# drumuino.net
KiCad netlist of a schematic drawn in EAGLE
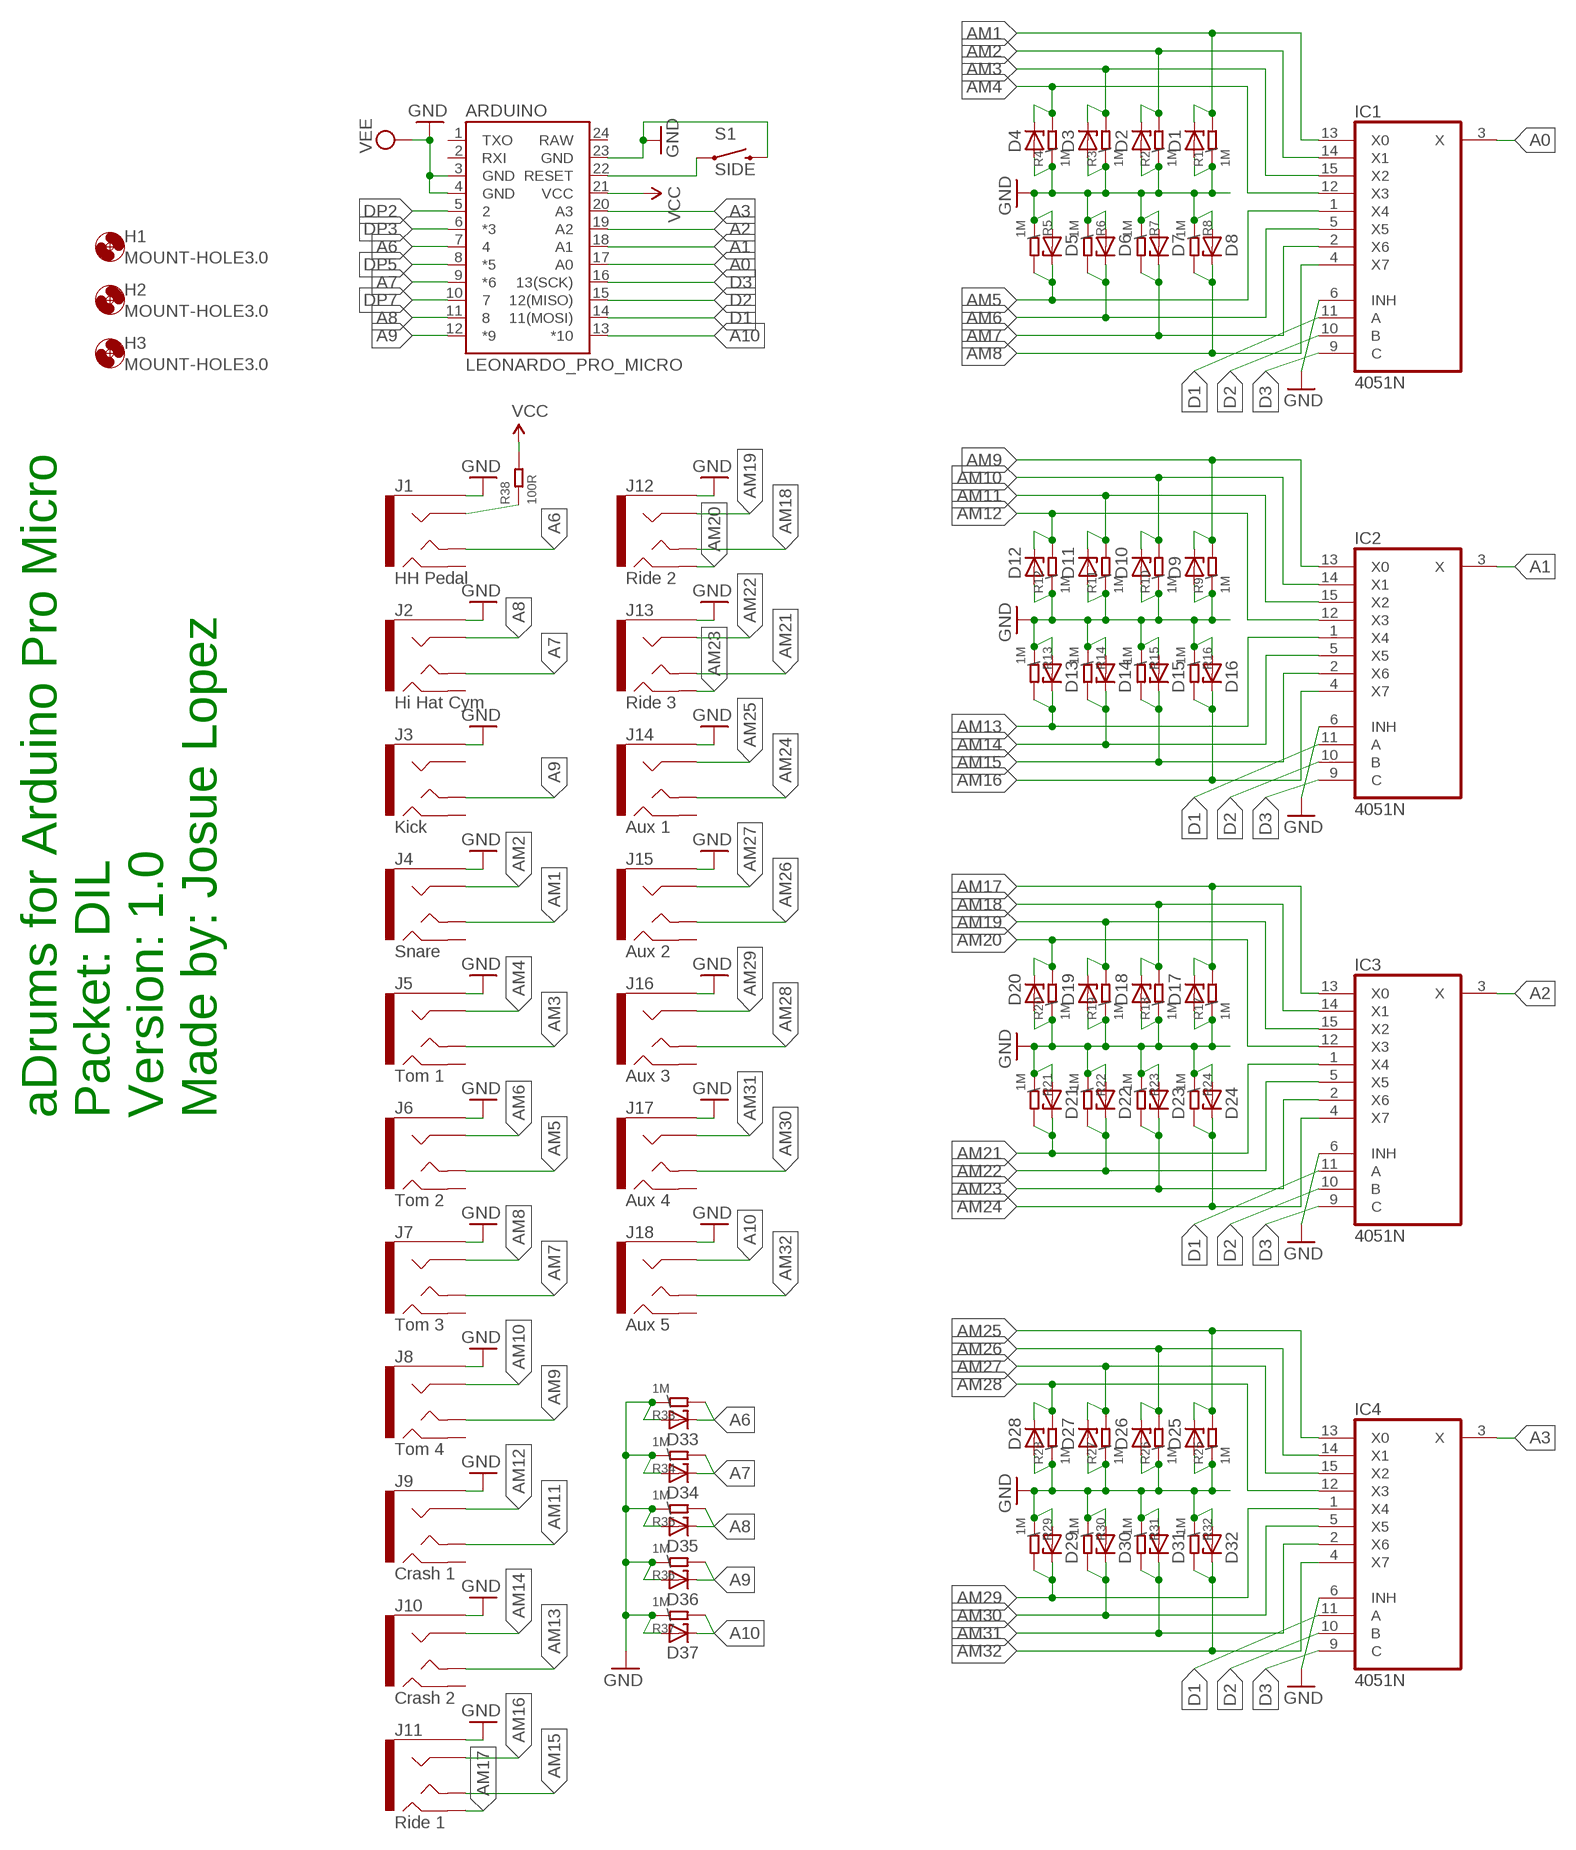
[diagram p0: schematic, sheet 1]

(export (version "E")
  (design (tool "Eeschema 10.0.6"))
  (components
    (comp (ref "ARDUINO")
      (value "LEONARDO_PRO_MICRO")
      (footprint "eagle-import:ARDUINO_PRO_MICRO")
      (libsource (lib "eagle-import") (part "ARDUINO_PRO_MICRO"))
    )
    (comp (ref "D1")
      (value "\\")
      (footprint "eagle-import:DO41-7.6")
      (libsource (lib "eagle-import") (part "ZENER-DIODEDO41-7.6"))
    )
    (comp (ref "D2")
      (value "\\")
      (footprint "eagle-import:DO41-7.6")
      (libsource (lib "eagle-import") (part "ZENER-DIODEDO41-7.6"))
    )
    (comp (ref "D3")
      (value "\\")
      (footprint "eagle-import:DO41-7.6")
      (libsource (lib "eagle-import") (part "ZENER-DIODEDO41-7.6"))
    )
    (comp (ref "D4")
      (value "\\")
      (footprint "eagle-import:DO41-7.6")
      (libsource (lib "eagle-import") (part "ZENER-DIODEDO41-7.6"))
    )
    (comp (ref "D5")
      (value "\\")
      (footprint "eagle-import:DO41-7.6")
      (libsource (lib "eagle-import") (part "ZENER-DIODEDO41-7.6"))
    )
    (comp (ref "D6")
      (value "\\")
      (footprint "eagle-import:DO41-7.6")
      (libsource (lib "eagle-import") (part "ZENER-DIODEDO41-7.6"))
    )
    (comp (ref "D7")
      (value "\\")
      (footprint "eagle-import:DO41-7.6")
      (libsource (lib "eagle-import") (part "ZENER-DIODEDO41-7.6"))
    )
    (comp (ref "D8")
      (value "\\")
      (footprint "eagle-import:DO41-7.6")
      (libsource (lib "eagle-import") (part "ZENER-DIODEDO41-7.6"))
    )
    (comp (ref "D9")
      (value "\\")
      (footprint "eagle-import:DO41-7.6")
      (libsource (lib "eagle-import") (part "ZENER-DIODEDO41-7.6"))
    )
    (comp (ref "D10")
      (value "\\")
      (footprint "eagle-import:DO41-7.6")
      (libsource (lib "eagle-import") (part "ZENER-DIODEDO41-7.6"))
    )
    (comp (ref "D11")
      (value "\\")
      (footprint "eagle-import:DO41-7.6")
      (libsource (lib "eagle-import") (part "ZENER-DIODEDO41-7.6"))
    )
    (comp (ref "D12")
      (value "\\")
      (footprint "eagle-import:DO41-7.6")
      (libsource (lib "eagle-import") (part "ZENER-DIODEDO41-7.6"))
    )
    (comp (ref "D13")
      (value "\\")
      (footprint "eagle-import:DO41-7.6")
      (libsource (lib "eagle-import") (part "ZENER-DIODEDO41-7.6"))
    )
    (comp (ref "D14")
      (value "\\")
      (footprint "eagle-import:DO41-7.6")
      (libsource (lib "eagle-import") (part "ZENER-DIODEDO41-7.6"))
    )
    (comp (ref "D15")
      (value "\\")
      (footprint "eagle-import:DO41-7.6")
      (libsource (lib "eagle-import") (part "ZENER-DIODEDO41-7.6"))
    )
    (comp (ref "D16")
      (value "\\")
      (footprint "eagle-import:DO41-7.6")
      (libsource (lib "eagle-import") (part "ZENER-DIODEDO41-7.6"))
    )
    (comp (ref "D17")
      (value "\\")
      (footprint "eagle-import:DO41-7.6")
      (libsource (lib "eagle-import") (part "ZENER-DIODEDO41-7.6"))
    )
    (comp (ref "D18")
      (value "\\")
      (footprint "eagle-import:DO41-7.6")
      (libsource (lib "eagle-import") (part "ZENER-DIODEDO41-7.6"))
    )
    (comp (ref "D19")
      (value "\\")
      (footprint "eagle-import:DO41-7.6")
      (libsource (lib "eagle-import") (part "ZENER-DIODEDO41-7.6"))
    )
    (comp (ref "D20")
      (value "\\")
      (footprint "eagle-import:DO41-7.6")
      (libsource (lib "eagle-import") (part "ZENER-DIODEDO41-7.6"))
    )
    (comp (ref "D21")
      (value "\\")
      (footprint "eagle-import:DO41-7.6")
      (libsource (lib "eagle-import") (part "ZENER-DIODEDO41-7.6"))
    )
    (comp (ref "D22")
      (value "\\")
      (footprint "eagle-import:DO41-7.6")
      (libsource (lib "eagle-import") (part "ZENER-DIODEDO41-7.6"))
    )
    (comp (ref "D23")
      (value "\\")
      (footprint "eagle-import:DO41-7.6")
      (libsource (lib "eagle-import") (part "ZENER-DIODEDO41-7.6"))
    )
    (comp (ref "D24")
      (value "\\")
      (footprint "eagle-import:DO41-7.6")
      (libsource (lib "eagle-import") (part "ZENER-DIODEDO41-7.6"))
    )
    (comp (ref "D25")
      (value "\\")
      (footprint "eagle-import:DO41-7.6")
      (libsource (lib "eagle-import") (part "ZENER-DIODEDO41-7.6"))
    )
    (comp (ref "D26")
      (value "\\")
      (footprint "eagle-import:DO41-7.6")
      (libsource (lib "eagle-import") (part "ZENER-DIODEDO41-7.6"))
    )
    (comp (ref "D27")
      (value "\\")
      (footprint "eagle-import:DO41-7.6")
      (libsource (lib "eagle-import") (part "ZENER-DIODEDO41-7.6"))
    )
    (comp (ref "D28")
      (value "\\")
      (footprint "eagle-import:DO41-7.6")
      (libsource (lib "eagle-import") (part "ZENER-DIODEDO41-7.6"))
    )
    (comp (ref "D29")
      (value "\\")
      (footprint "eagle-import:DO41-7.6")
      (libsource (lib "eagle-import") (part "ZENER-DIODEDO41-7.6"))
    )
    (comp (ref "D30")
      (value "\\")
      (footprint "eagle-import:DO41-7.6")
      (libsource (lib "eagle-import") (part "ZENER-DIODEDO41-7.6"))
    )
    (comp (ref "D31")
      (value "\\")
      (footprint "eagle-import:DO41-7.6")
      (libsource (lib "eagle-import") (part "ZENER-DIODEDO41-7.6"))
    )
    (comp (ref "D32")
      (value "\\")
      (footprint "eagle-import:DO41-7.6")
      (libsource (lib "eagle-import") (part "ZENER-DIODEDO41-7.6"))
    )
    (comp (ref "D33")
      (value "\\")
      (footprint "eagle-import:DO41-7.6")
      (libsource (lib "eagle-import") (part "ZENER-DIODEDO41-7.6"))
    )
    (comp (ref "D34")
      (value "\\")
      (footprint "eagle-import:DO41-7.6")
      (libsource (lib "eagle-import") (part "ZENER-DIODEDO41-7.6"))
    )
    (comp (ref "D35")
      (value "\\")
      (footprint "eagle-import:DO41-7.6")
      (libsource (lib "eagle-import") (part "ZENER-DIODEDO41-7.6"))
    )
    (comp (ref "D36")
      (value "\\")
      (footprint "eagle-import:DO41-7.6")
      (libsource (lib "eagle-import") (part "ZENER-DIODEDO41-7.6"))
    )
    (comp (ref "D37")
      (value "\\")
      (footprint "eagle-import:DO41-7.6")
      (libsource (lib "eagle-import") (part "ZENER-DIODEDO41-7.6"))
    )
    (comp (ref "H1")
      (value "MOUNT-HOLE3.0")
      (footprint "eagle-import:3,0")
      (libsource (lib "eagle-import") (part "MOUNT-HOLE3.0"))
    )
    (comp (ref "H2")
      (value "MOUNT-HOLE3.0")
      (footprint "eagle-import:3,0")
      (libsource (lib "eagle-import") (part "MOUNT-HOLE3.0"))
    )
    (comp (ref "H3")
      (value "MOUNT-HOLE3.0")
      (footprint "eagle-import:3,0")
      (libsource (lib "eagle-import") (part "MOUNT-HOLE3.0"))
    )
    (comp (ref "IC1")
      (value "4051N")
      (footprint "eagle-import:DIL16")
      (libsource (lib "eagle-import") (part "4051N"))
    )
    (comp (ref "IC2")
      (value "4051N")
      (footprint "eagle-import:DIL16")
      (libsource (lib "eagle-import") (part "4051N"))
    )
    (comp (ref "IC3")
      (value "4051N")
      (footprint "eagle-import:DIL16")
      (libsource (lib "eagle-import") (part "4051N"))
    )
    (comp (ref "IC4")
      (value "4051N")
      (footprint "eagle-import:DIL16")
      (libsource (lib "eagle-import") (part "4051N"))
    )
    (comp (ref "J1")
      (value "HH Pedal")
      (footprint "eagle-import:AUDIO-JACK-TRRS-DIL")
      (libsource (lib "eagle-import") (part "AUDIO-JACK3'DIL'"))
    )
    (comp (ref "J2")
      (value "Hi Hat Cym")
      (footprint "eagle-import:AUDIO-JACK-TRRS-DIL")
      (libsource (lib "eagle-import") (part "AUDIO-JACK3'DIL'"))
    )
    (comp (ref "J3")
      (value "Kick")
      (footprint "eagle-import:AUDIO-JACK-TRRS-DIL")
      (libsource (lib "eagle-import") (part "AUDIO-JACK3'DIL'"))
    )
    (comp (ref "J4")
      (value "Snare")
      (footprint "eagle-import:AUDIO-JACK-TRRS-DIL")
      (libsource (lib "eagle-import") (part "AUDIO-JACK3'DIL'"))
    )
    (comp (ref "J5")
      (value "Tom 1")
      (footprint "eagle-import:AUDIO-JACK-TRRS-DIL")
      (libsource (lib "eagle-import") (part "AUDIO-JACK3'DIL'"))
    )
    (comp (ref "J6")
      (value "Tom 2")
      (footprint "eagle-import:AUDIO-JACK-TRRS-DIL")
      (libsource (lib "eagle-import") (part "AUDIO-JACK3'DIL'"))
    )
    (comp (ref "J7")
      (value "Tom 3")
      (footprint "eagle-import:AUDIO-JACK-TRRS-DIL")
      (libsource (lib "eagle-import") (part "AUDIO-JACK3'DIL'"))
    )
    (comp (ref "J8")
      (value "Tom 4")
      (footprint "eagle-import:AUDIO-JACK-TRRS-DIL")
      (libsource (lib "eagle-import") (part "AUDIO-JACK3'DIL'"))
    )
    (comp (ref "J9")
      (value "Crash 1")
      (footprint "eagle-import:AUDIO-JACK-TRRS-DIL")
      (libsource (lib "eagle-import") (part "AUDIO-JACK3'DIL'"))
    )
    (comp (ref "J10")
      (value "Crash 2")
      (footprint "eagle-import:AUDIO-JACK-TRRS-DIL")
      (libsource (lib "eagle-import") (part "AUDIO-JACK3'DIL'"))
    )
    (comp (ref "J11")
      (value "Ride 1")
      (footprint "eagle-import:AUDIO-JACK-TRRS-DIL")
      (libsource (lib "eagle-import") (part "AUDIO-JACK3'DIL'"))
    )
    (comp (ref "J12")
      (value "Ride 2")
      (footprint "eagle-import:AUDIO-JACK-TRRS-DIL")
      (libsource (lib "eagle-import") (part "AUDIO-JACK3'DIL'"))
    )
    (comp (ref "J13")
      (value "Ride 3")
      (footprint "eagle-import:AUDIO-JACK-TRRS-DIL")
      (libsource (lib "eagle-import") (part "AUDIO-JACK3'DIL'"))
    )
    (comp (ref "J14")
      (value "Aux 1")
      (footprint "eagle-import:AUDIO-JACK-TRRS-DIL")
      (libsource (lib "eagle-import") (part "AUDIO-JACK3'DIL'"))
    )
    (comp (ref "J15")
      (value "Aux 2")
      (footprint "eagle-import:AUDIO-JACK-TRRS-DIL")
      (libsource (lib "eagle-import") (part "AUDIO-JACK3'DIL'"))
    )
    (comp (ref "J16")
      (value "Aux 3")
      (footprint "eagle-import:AUDIO-JACK-TRRS-DIL")
      (libsource (lib "eagle-import") (part "AUDIO-JACK3'DIL'"))
    )
    (comp (ref "J17")
      (value "Aux 4")
      (footprint "eagle-import:AUDIO-JACK-TRRS-DIL")
      (libsource (lib "eagle-import") (part "AUDIO-JACK3'DIL'"))
    )
    (comp (ref "J18")
      (value "Aux 5")
      (footprint "eagle-import:AUDIO-JACK-TRRS-DIL")
      (libsource (lib "eagle-import") (part "AUDIO-JACK3'DIL'"))
    )
    (comp (ref "R1")
      (value "1M")
      (footprint "eagle-import:R0207_7")
      (libsource (lib "eagle-import") (part "RES-0207/7"))
    )
    (comp (ref "R2")
      (value "1M")
      (footprint "eagle-import:R0207_7")
      (libsource (lib "eagle-import") (part "RES-0207/7"))
    )
    (comp (ref "R3")
      (value "1M")
      (footprint "eagle-import:R0207_7")
      (libsource (lib "eagle-import") (part "RES-0207/7"))
    )
    (comp (ref "R4")
      (value "1M")
      (footprint "eagle-import:R0207_7")
      (libsource (lib "eagle-import") (part "RES-0207/7"))
    )
    (comp (ref "R5")
      (value "1M")
      (footprint "eagle-import:R0207_7")
      (libsource (lib "eagle-import") (part "RES-0207/7"))
    )
    (comp (ref "R6")
      (value "1M")
      (footprint "eagle-import:R0207_7")
      (libsource (lib "eagle-import") (part "RES-0207/7"))
    )
    (comp (ref "R7")
      (value "1M")
      (footprint "eagle-import:R0207_7")
      (libsource (lib "eagle-import") (part "RES-0207/7"))
    )
    (comp (ref "R8")
      (value "1M")
      (footprint "eagle-import:R0207_7")
      (libsource (lib "eagle-import") (part "RES-0207/7"))
    )
    (comp (ref "R9")
      (value "1M")
      (footprint "eagle-import:R0207_7")
      (libsource (lib "eagle-import") (part "RES-0207/7"))
    )
    (comp (ref "R10")
      (value "1M")
      (footprint "eagle-import:R0207_7")
      (libsource (lib "eagle-import") (part "RES-0207/7"))
    )
    (comp (ref "R11")
      (value "1M")
      (footprint "eagle-import:R0207_7")
      (libsource (lib "eagle-import") (part "RES-0207/7"))
    )
    (comp (ref "R12")
      (value "1M")
      (footprint "eagle-import:R0207_7")
      (libsource (lib "eagle-import") (part "RES-0207/7"))
    )
    (comp (ref "R13")
      (value "1M")
      (footprint "eagle-import:R0207_7")
      (libsource (lib "eagle-import") (part "RES-0207/7"))
    )
    (comp (ref "R14")
      (value "1M")
      (footprint "eagle-import:R0207_7")
      (libsource (lib "eagle-import") (part "RES-0207/7"))
    )
    (comp (ref "R15")
      (value "1M")
      (footprint "eagle-import:R0207_7")
      (libsource (lib "eagle-import") (part "RES-0207/7"))
    )
    (comp (ref "R16")
      (value "1M")
      (footprint "eagle-import:R0207_7")
      (libsource (lib "eagle-import") (part "RES-0207/7"))
    )
    (comp (ref "R17")
      (value "1M")
      (footprint "eagle-import:R0207_7")
      (libsource (lib "eagle-import") (part "RES-0207/7"))
    )
    (comp (ref "R18")
      (value "1M")
      (footprint "eagle-import:R0207_7")
      (libsource (lib "eagle-import") (part "RES-0207/7"))
    )
    (comp (ref "R19")
      (value "1M")
      (footprint "eagle-import:R0207_7")
      (libsource (lib "eagle-import") (part "RES-0207/7"))
    )
    (comp (ref "R20")
      (value "1M")
      (footprint "eagle-import:R0207_7")
      (libsource (lib "eagle-import") (part "RES-0207/7"))
    )
    (comp (ref "R21")
      (value "1M")
      (footprint "eagle-import:R0207_7")
      (libsource (lib "eagle-import") (part "RES-0207/7"))
    )
    (comp (ref "R22")
      (value "1M")
      (footprint "eagle-import:R0207_7")
      (libsource (lib "eagle-import") (part "RES-0207/7"))
    )
    (comp (ref "R23")
      (value "1M")
      (footprint "eagle-import:R0207_7")
      (libsource (lib "eagle-import") (part "RES-0207/7"))
    )
    (comp (ref "R24")
      (value "1M")
      (footprint "eagle-import:R0207_7")
      (libsource (lib "eagle-import") (part "RES-0207/7"))
    )
    (comp (ref "R25")
      (value "1M")
      (footprint "eagle-import:R0207_7")
      (libsource (lib "eagle-import") (part "RES-0207/7"))
    )
    (comp (ref "R26")
      (value "1M")
      (footprint "eagle-import:R0207_7")
      (libsource (lib "eagle-import") (part "RES-0207/7"))
    )
    (comp (ref "R27")
      (value "1M")
      (footprint "eagle-import:R0207_7")
      (libsource (lib "eagle-import") (part "RES-0207/7"))
    )
    (comp (ref "R28")
      (value "1M")
      (footprint "eagle-import:R0207_7")
      (libsource (lib "eagle-import") (part "RES-0207/7"))
    )
    (comp (ref "R29")
      (value "1M")
      (footprint "eagle-import:R0207_7")
      (libsource (lib "eagle-import") (part "RES-0207/7"))
    )
    (comp (ref "R30")
      (value "1M")
      (footprint "eagle-import:R0207_7")
      (libsource (lib "eagle-import") (part "RES-0207/7"))
    )
    (comp (ref "R31")
      (value "1M")
      (footprint "eagle-import:R0207_7")
      (libsource (lib "eagle-import") (part "RES-0207/7"))
    )
    (comp (ref "R32")
      (value "1M")
      (footprint "eagle-import:R0207_7")
      (libsource (lib "eagle-import") (part "RES-0207/7"))
    )
    (comp (ref "R33")
      (value "1M")
      (footprint "eagle-import:R0207_7")
      (libsource (lib "eagle-import") (part "RES-0207/7"))
    )
    (comp (ref "R34")
      (value "1M")
      (footprint "eagle-import:R0207_7")
      (libsource (lib "eagle-import") (part "RES-0207/7"))
    )
    (comp (ref "R35")
      (value "1M")
      (footprint "eagle-import:R0207_7")
      (libsource (lib "eagle-import") (part "RES-0207/7"))
    )
    (comp (ref "R36")
      (value "1M")
      (footprint "eagle-import:R0207_7")
      (libsource (lib "eagle-import") (part "RES-0207/7"))
    )
    (comp (ref "R37")
      (value "1M")
      (footprint "eagle-import:R0207_7")
      (libsource (lib "eagle-import") (part "RES-0207/7"))
    )
    (comp (ref "R38")
      (value "100R")
      (footprint "eagle-import:R0207_7")
      (libsource (lib "eagle-import") (part "RES-0207/7"))
    )
    (comp (ref "S1")
      (value "SIDE")
      (footprint "eagle-import:TACTILE-PTH-SIDEEZ")
      (libsource (lib "eagle-import") (part "SWITCH-MOMENTARY-2SIDE_EZ"))
    )
  )
  (nets
    (net (code "1") (name "A0") (class "Default")
      (node (ref "ARDUINO") (pin "17") (pinfunction "A0_17") (pintype "bidirectional"))
      (node (ref "IC1") (pin "3") (pinfunction "X_3") (pintype "bidirectional"))
    )
    (net (code "2") (name "A1") (class "Default")
      (node (ref "ARDUINO") (pin "18") (pinfunction "A1_18") (pintype "bidirectional"))
      (node (ref "IC2") (pin "3") (pinfunction "X_3") (pintype "bidirectional"))
    )
    (net (code "3") (name "A2") (class "Default")
      (node (ref "ARDUINO") (pin "19") (pinfunction "A2_19") (pintype "bidirectional"))
      (node (ref "IC3") (pin "3") (pinfunction "X_3") (pintype "bidirectional"))
    )
    (net (code "4") (name "A3") (class "Default")
      (node (ref "ARDUINO") (pin "20") (pinfunction "A3_20") (pintype "bidirectional"))
      (node (ref "IC4") (pin "3") (pinfunction "X_3") (pintype "bidirectional"))
    )
    (net (code "5") (name "A6") (class "Default")
      (node (ref "ARDUINO") (pin "7") (pinfunction "4_7") (pintype "bidirectional"))
      (node (ref "D33") (pin "C") (pinfunction "C_C") (pintype "passive"))
      (node (ref "J1") (pin "TIP") (pinfunction "TIP_TIP") (pintype "bidirectional"))
      (node (ref "R33") (pin "2") (pinfunction "2_2") (pintype "passive"))
    )
    (net (code "6") (name "A7") (class "Default")
      (node (ref "ARDUINO") (pin "9") (pinfunction "*6_9") (pintype "bidirectional"))
      (node (ref "D34") (pin "C") (pinfunction "C_C") (pintype "passive"))
      (node (ref "J2") (pin "TIP") (pinfunction "TIP_TIP") (pintype "bidirectional"))
      (node (ref "R34") (pin "2") (pinfunction "2_2") (pintype "passive"))
    )
    (net (code "7") (name "A8") (class "Default")
      (node (ref "ARDUINO") (pin "11") (pinfunction "8_11") (pintype "bidirectional"))
      (node (ref "D35") (pin "C") (pinfunction "C_C") (pintype "passive"))
      (node (ref "J2") (pin "RING1") (pinfunction "RING1_RING1") (pintype "bidirectional"))
      (node (ref "R35") (pin "2") (pinfunction "2_2") (pintype "passive"))
    )
    (net (code "8") (name "A9") (class "Default")
      (node (ref "ARDUINO") (pin "12") (pinfunction "*9_12") (pintype "bidirectional"))
      (node (ref "D36") (pin "C") (pinfunction "C_C") (pintype "passive"))
      (node (ref "J3") (pin "TIP") (pinfunction "TIP_TIP") (pintype "bidirectional"))
      (node (ref "R36") (pin "2") (pinfunction "2_2") (pintype "passive"))
    )
    (net (code "9") (name "A10") (class "Default")
      (node (ref "ARDUINO") (pin "13") (pinfunction "*10_13") (pintype "bidirectional"))
      (node (ref "D37") (pin "C") (pinfunction "C_C") (pintype "passive"))
      (node (ref "J18") (pin "RING1") (pinfunction "RING1_RING1") (pintype "bidirectional"))
      (node (ref "R37") (pin "2") (pinfunction "2_2") (pintype "passive"))
    )
    (net (code "10") (name "AM1") (class "Default")
      (node (ref "D1") (pin "C") (pinfunction "C_C") (pintype "passive"))
      (node (ref "IC1") (pin "13") (pinfunction "X0_13") (pintype "bidirectional"))
      (node (ref "J4") (pin "TIP") (pinfunction "TIP_TIP") (pintype "bidirectional"))
      (node (ref "R1") (pin "2") (pinfunction "2_2") (pintype "passive"))
    )
    (net (code "11") (name "AM2") (class "Default")
      (node (ref "D2") (pin "C") (pinfunction "C_C") (pintype "passive"))
      (node (ref "IC1") (pin "14") (pinfunction "X1_14") (pintype "bidirectional"))
      (node (ref "J4") (pin "RING1") (pinfunction "RING1_RING1") (pintype "bidirectional"))
      (node (ref "R2") (pin "2") (pinfunction "2_2") (pintype "passive"))
    )
    (net (code "12") (name "AM3") (class "Default")
      (node (ref "D3") (pin "C") (pinfunction "C_C") (pintype "passive"))
      (node (ref "IC1") (pin "15") (pinfunction "X2_15") (pintype "bidirectional"))
      (node (ref "J5") (pin "TIP") (pinfunction "TIP_TIP") (pintype "bidirectional"))
      (node (ref "R3") (pin "2") (pinfunction "2_2") (pintype "passive"))
    )
    (net (code "13") (name "AM4") (class "Default")
      (node (ref "D4") (pin "C") (pinfunction "C_C") (pintype "passive"))
      (node (ref "IC1") (pin "12") (pinfunction "X3_12") (pintype "bidirectional"))
      (node (ref "J5") (pin "RING1") (pinfunction "RING1_RING1") (pintype "bidirectional"))
      (node (ref "R4") (pin "2") (pinfunction "2_2") (pintype "passive"))
    )
    (net (code "14") (name "AM5") (class "Default")
      (node (ref "D5") (pin "C") (pinfunction "C_C") (pintype "passive"))
      (node (ref "IC1") (pin "1") (pinfunction "X4_1") (pintype "bidirectional"))
      (node (ref "J6") (pin "TIP") (pinfunction "TIP_TIP") (pintype "bidirectional"))
      (node (ref "R5") (pin "2") (pinfunction "2_2") (pintype "passive"))
    )
    (net (code "15") (name "AM6") (class "Default")
      (node (ref "D6") (pin "C") (pinfunction "C_C") (pintype "passive"))
      (node (ref "IC1") (pin "5") (pinfunction "X5_5") (pintype "bidirectional"))
      (node (ref "J6") (pin "RING1") (pinfunction "RING1_RING1") (pintype "bidirectional"))
      (node (ref "R6") (pin "2") (pinfunction "2_2") (pintype "passive"))
    )
    (net (code "16") (name "AM7") (class "Default")
      (node (ref "D7") (pin "C") (pinfunction "C_C") (pintype "passive"))
      (node (ref "IC1") (pin "2") (pinfunction "X6_2") (pintype "bidirectional"))
      (node (ref "J7") (pin "TIP") (pinfunction "TIP_TIP") (pintype "bidirectional"))
      (node (ref "R7") (pin "2") (pinfunction "2_2") (pintype "passive"))
    )
    (net (code "17") (name "AM8") (class "Default")
      (node (ref "D8") (pin "C") (pinfunction "C_C") (pintype "passive"))
      (node (ref "IC1") (pin "4") (pinfunction "X7_4") (pintype "bidirectional"))
      (node (ref "J7") (pin "RING1") (pinfunction "RING1_RING1") (pintype "bidirectional"))
      (node (ref "R8") (pin "2") (pinfunction "2_2") (pintype "passive"))
    )
    (net (code "18") (name "AM9") (class "Default")
      (node (ref "D9") (pin "C") (pinfunction "C_C") (pintype "passive"))
      (node (ref "IC2") (pin "13") (pinfunction "X0_13") (pintype "bidirectional"))
      (node (ref "J8") (pin "TIP") (pinfunction "TIP_TIP") (pintype "bidirectional"))
      (node (ref "R9") (pin "2") (pinfunction "2_2") (pintype "passive"))
    )
    (net (code "19") (name "AM10") (class "Default")
      (node (ref "D10") (pin "C") (pinfunction "C_C") (pintype "passive"))
      (node (ref "IC2") (pin "14") (pinfunction "X1_14") (pintype "bidirectional"))
      (node (ref "J8") (pin "RING1") (pinfunction "RING1_RING1") (pintype "bidirectional"))
      (node (ref "R10") (pin "2") (pinfunction "2_2") (pintype "passive"))
    )
    (net (code "20") (name "AM11") (class "Default")
      (node (ref "D11") (pin "C") (pinfunction "C_C") (pintype "passive"))
      (node (ref "IC2") (pin "15") (pinfunction "X2_15") (pintype "bidirectional"))
      (node (ref "J9") (pin "TIP") (pinfunction "TIP_TIP") (pintype "bidirectional"))
      (node (ref "R11") (pin "2") (pinfunction "2_2") (pintype "passive"))
    )
    (net (code "21") (name "AM12") (class "Default")
      (node (ref "D12") (pin "C") (pinfunction "C_C") (pintype "passive"))
      (node (ref "IC2") (pin "12") (pinfunction "X3_12") (pintype "bidirectional"))
      (node (ref "J9") (pin "RING1") (pinfunction "RING1_RING1") (pintype "bidirectional"))
      (node (ref "R12") (pin "2") (pinfunction "2_2") (pintype "passive"))
    )
    (net (code "22") (name "AM13") (class "Default")
      (node (ref "D13") (pin "C") (pinfunction "C_C") (pintype "passive"))
      (node (ref "IC2") (pin "1") (pinfunction "X4_1") (pintype "bidirectional"))
      (node (ref "J10") (pin "TIP") (pinfunction "TIP_TIP") (pintype "bidirectional"))
      (node (ref "R13") (pin "2") (pinfunction "2_2") (pintype "passive"))
    )
    (net (code "23") (name "AM14") (class "Default")
      (node (ref "D14") (pin "C") (pinfunction "C_C") (pintype "passive"))
      (node (ref "IC2") (pin "5") (pinfunction "X5_5") (pintype "bidirectional"))
      (node (ref "J10") (pin "RING1") (pinfunction "RING1_RING1") (pintype "bidirectional"))
      (node (ref "R14") (pin "2") (pinfunction "2_2") (pintype "passive"))
    )
    (net (code "24") (name "AM15") (class "Default")
      (node (ref "D15") (pin "C") (pinfunction "C_C") (pintype "passive"))
      (node (ref "IC2") (pin "2") (pinfunction "X6_2") (pintype "bidirectional"))
      (node (ref "J11") (pin "TIP") (pinfunction "TIP_TIP") (pintype "bidirectional"))
      (node (ref "R15") (pin "2") (pinfunction "2_2") (pintype "passive"))
    )
    (net (code "25") (name "AM16") (class "Default")
      (node (ref "D16") (pin "C") (pinfunction "C_C") (pintype "passive"))
      (node (ref "IC2") (pin "4") (pinfunction "X7_4") (pintype "bidirectional"))
      (node (ref "J11") (pin "RING1") (pinfunction "RING1_RING1") (pintype "bidirectional"))
      (node (ref "R16") (pin "2") (pinfunction "2_2") (pintype "passive"))
    )
    (net (code "26") (name "AM17") (class "Default")
      (node (ref "D17") (pin "C") (pinfunction "C_C") (pintype "passive"))
      (node (ref "IC3") (pin "13") (pinfunction "X0_13") (pintype "bidirectional"))
      (node (ref "J11") (pin "RING2") (pinfunction "RING2_RING2") (pintype "bidirectional"))
      (node (ref "R17") (pin "2") (pinfunction "2_2") (pintype "passive"))
    )
    (net (code "27") (name "AM18") (class "Default")
      (node (ref "D18") (pin "C") (pinfunction "C_C") (pintype "passive"))
      (node (ref "IC3") (pin "14") (pinfunction "X1_14") (pintype "bidirectional"))
      (node (ref "J12") (pin "TIP") (pinfunction "TIP_TIP") (pintype "bidirectional"))
      (node (ref "R18") (pin "2") (pinfunction "2_2") (pintype "passive"))
    )
    (net (code "28") (name "AM19") (class "Default")
      (node (ref "D19") (pin "C") (pinfunction "C_C") (pintype "passive"))
      (node (ref "IC3") (pin "15") (pinfunction "X2_15") (pintype "bidirectional"))
      (node (ref "J12") (pin "RING1") (pinfunction "RING1_RING1") (pintype "bidirectional"))
      (node (ref "R19") (pin "2") (pinfunction "2_2") (pintype "passive"))
    )
    (net (code "29") (name "AM20") (class "Default")
      (node (ref "D20") (pin "C") (pinfunction "C_C") (pintype "passive"))
      (node (ref "IC3") (pin "12") (pinfunction "X3_12") (pintype "bidirectional"))
      (node (ref "J12") (pin "RING2") (pinfunction "RING2_RING2") (pintype "bidirectional"))
      (node (ref "R20") (pin "2") (pinfunction "2_2") (pintype "passive"))
    )
    (net (code "30") (name "AM21") (class "Default")
      (node (ref "D21") (pin "C") (pinfunction "C_C") (pintype "passive"))
      (node (ref "IC3") (pin "1") (pinfunction "X4_1") (pintype "bidirectional"))
      (node (ref "J13") (pin "TIP") (pinfunction "TIP_TIP") (pintype "bidirectional"))
      (node (ref "R21") (pin "2") (pinfunction "2_2") (pintype "passive"))
    )
    (net (code "31") (name "AM22") (class "Default")
      (node (ref "D22") (pin "C") (pinfunction "C_C") (pintype "passive"))
      (node (ref "IC3") (pin "5") (pinfunction "X5_5") (pintype "bidirectional"))
      (node (ref "J13") (pin "RING1") (pinfunction "RING1_RING1") (pintype "bidirectional"))
      (node (ref "R22") (pin "2") (pinfunction "2_2") (pintype "passive"))
    )
    (net (code "32") (name "AM23") (class "Default")
      (node (ref "D23") (pin "C") (pinfunction "C_C") (pintype "passive"))
      (node (ref "IC3") (pin "2") (pinfunction "X6_2") (pintype "bidirectional"))
      (node (ref "J13") (pin "RING2") (pinfunction "RING2_RING2") (pintype "bidirectional"))
      (node (ref "R23") (pin "2") (pinfunction "2_2") (pintype "passive"))
    )
    (net (code "33") (name "AM24") (class "Default")
      (node (ref "D24") (pin "C") (pinfunction "C_C") (pintype "passive"))
      (node (ref "IC3") (pin "4") (pinfunction "X7_4") (pintype "bidirectional"))
      (node (ref "J14") (pin "TIP") (pinfunction "TIP_TIP") (pintype "bidirectional"))
      (node (ref "R24") (pin "2") (pinfunction "2_2") (pintype "passive"))
    )
    (net (code "34") (name "AM25") (class "Default")
      (node (ref "D25") (pin "C") (pinfunction "C_C") (pintype "passive"))
      (node (ref "IC4") (pin "13") (pinfunction "X0_13") (pintype "bidirectional"))
      (node (ref "J14") (pin "RING1") (pinfunction "RING1_RING1") (pintype "bidirectional"))
      (node (ref "R25") (pin "2") (pinfunction "2_2") (pintype "passive"))
    )
    (net (code "35") (name "AM26") (class "Default")
      (node (ref "D26") (pin "C") (pinfunction "C_C") (pintype "passive"))
      (node (ref "IC4") (pin "14") (pinfunction "X1_14") (pintype "bidirectional"))
      (node (ref "J15") (pin "TIP") (pinfunction "TIP_TIP") (pintype "bidirectional"))
      (node (ref "R26") (pin "2") (pinfunction "2_2") (pintype "passive"))
    )
    (net (code "36") (name "AM27") (class "Default")
      (node (ref "D27") (pin "C") (pinfunction "C_C") (pintype "passive"))
      (node (ref "IC4") (pin "15") (pinfunction "X2_15") (pintype "bidirectional"))
      (node (ref "J15") (pin "RING1") (pinfunction "RING1_RING1") (pintype "bidirectional"))
      (node (ref "R27") (pin "2") (pinfunction "2_2") (pintype "passive"))
    )
    (net (code "37") (name "AM28") (class "Default")
      (node (ref "D28") (pin "C") (pinfunction "C_C") (pintype "passive"))
      (node (ref "IC4") (pin "12") (pinfunction "X3_12") (pintype "bidirectional"))
      (node (ref "J16") (pin "TIP") (pinfunction "TIP_TIP") (pintype "bidirectional"))
      (node (ref "R28") (pin "2") (pinfunction "2_2") (pintype "passive"))
    )
    (net (code "38") (name "AM29") (class "Default")
      (node (ref "D29") (pin "C") (pinfunction "C_C") (pintype "passive"))
      (node (ref "IC4") (pin "1") (pinfunction "X4_1") (pintype "bidirectional"))
      (node (ref "J16") (pin "RING1") (pinfunction "RING1_RING1") (pintype "bidirectional"))
      (node (ref "R29") (pin "2") (pinfunction "2_2") (pintype "passive"))
    )
    (net (code "39") (name "AM30") (class "Default")
      (node (ref "D30") (pin "C") (pinfunction "C_C") (pintype "passive"))
      (node (ref "IC4") (pin "5") (pinfunction "X5_5") (pintype "bidirectional"))
      (node (ref "J17") (pin "TIP") (pinfunction "TIP_TIP") (pintype "bidirectional"))
      (node (ref "R30") (pin "2") (pinfunction "2_2") (pintype "passive"))
    )
    (net (code "40") (name "AM31") (class "Default")
      (node (ref "D31") (pin "C") (pinfunction "C_C") (pintype "passive"))
      (node (ref "IC4") (pin "2") (pinfunction "X6_2") (pintype "bidirectional"))
      (node (ref "J17") (pin "RING1") (pinfunction "RING1_RING1") (pintype "bidirectional"))
      (node (ref "R31") (pin "2") (pinfunction "2_2") (pintype "passive"))
    )
    (net (code "41") (name "AM32") (class "Default")
      (node (ref "D32") (pin "C") (pinfunction "C_C") (pintype "passive"))
      (node (ref "IC4") (pin "4") (pinfunction "X7_4") (pintype "bidirectional"))
      (node (ref "J18") (pin "TIP") (pinfunction "TIP_TIP") (pintype "bidirectional"))
      (node (ref "R32") (pin "2") (pinfunction "2_2") (pintype "passive"))
    )
    (net (code "42") (name "D1") (class "Default")
      (node (ref "ARDUINO") (pin "14") (pinfunction "11(MOSI)_14") (pintype "bidirectional"))
      (node (ref "IC1") (pin "11") (pinfunction "A_11") (pintype "input"))
      (node (ref "IC2") (pin "11") (pinfunction "A_11") (pintype "input"))
      (node (ref "IC3") (pin "11") (pinfunction "A_11") (pintype "input"))
      (node (ref "IC4") (pin "11") (pinfunction "A_11") (pintype "input"))
    )
    (net (code "43") (name "D2") (class "Default")
      (node (ref "ARDUINO") (pin "15") (pinfunction "12(MISO)_15") (pintype "bidirectional"))
      (node (ref "IC1") (pin "10") (pinfunction "B_10") (pintype "input"))
      (node (ref "IC2") (pin "10") (pinfunction "B_10") (pintype "input"))
      (node (ref "IC3") (pin "10") (pinfunction "B_10") (pintype "input"))
      (node (ref "IC4") (pin "10") (pinfunction "B_10") (pintype "input"))
    )
    (net (code "44") (name "D3") (class "Default")
      (node (ref "ARDUINO") (pin "16") (pinfunction "13(SCK)_16") (pintype "bidirectional"))
      (node (ref "IC1") (pin "9") (pinfunction "C_9") (pintype "input"))
      (node (ref "IC2") (pin "9") (pinfunction "C_9") (pintype "input"))
      (node (ref "IC3") (pin "9") (pinfunction "C_9") (pintype "input"))
      (node (ref "IC4") (pin "9") (pinfunction "C_9") (pintype "input"))
    )
    (net (code "45") (name "DP2") (class "Default")
      (node (ref "ARDUINO") (pin "5") (pinfunction "2_5") (pintype "bidirectional"))
    )
    (net (code "46") (name "DP3") (class "Default")
      (node (ref "ARDUINO") (pin "6") (pinfunction "*3_6") (pintype "bidirectional"))
    )
    (net (code "47") (name "DP5") (class "Default")
      (node (ref "ARDUINO") (pin "8") (pinfunction "*5_8") (pintype "bidirectional"))
    )
    (net (code "48") (name "DP7") (class "Default")
      (node (ref "ARDUINO") (pin "10") (pinfunction "7_10") (pintype "bidirectional"))
    )
    (net (code "49") (name "GND") (class "Default")
      (node (ref "ARDUINO") (pin "23") (pinfunction "GND_23") (pintype "bidirectional"))
      (node (ref "ARDUINO") (pin "3") (pinfunction "GND_3") (pintype "bidirectional"))
      (node (ref "ARDUINO") (pin "4") (pinfunction "GND_4") (pintype "bidirectional"))
      (node (ref "D1") (pin "A") (pinfunction "A_A") (pintype "passive"))
      (node (ref "D10") (pin "A") (pinfunction "A_A") (pintype "passive"))
      (node (ref "D11") (pin "A") (pinfunction "A_A") (pintype "passive"))
      (node (ref "D12") (pin "A") (pinfunction "A_A") (pintype "passive"))
      (node (ref "D13") (pin "A") (pinfunction "A_A") (pintype "passive"))
      (node (ref "D14") (pin "A") (pinfunction "A_A") (pintype "passive"))
      (node (ref "D15") (pin "A") (pinfunction "A_A") (pintype "passive"))
      (node (ref "D16") (pin "A") (pinfunction "A_A") (pintype "passive"))
      (node (ref "D17") (pin "A") (pinfunction "A_A") (pintype "passive"))
      (node (ref "D18") (pin "A") (pinfunction "A_A") (pintype "passive"))
      (node (ref "D19") (pin "A") (pinfunction "A_A") (pintype "passive"))
      (node (ref "D2") (pin "A") (pinfunction "A_A") (pintype "passive"))
      (node (ref "D20") (pin "A") (pinfunction "A_A") (pintype "passive"))
      (node (ref "D21") (pin "A") (pinfunction "A_A") (pintype "passive"))
      (node (ref "D22") (pin "A") (pinfunction "A_A") (pintype "passive"))
      (node (ref "D23") (pin "A") (pinfunction "A_A") (pintype "passive"))
      (node (ref "D24") (pin "A") (pinfunction "A_A") (pintype "passive"))
      (node (ref "D25") (pin "A") (pinfunction "A_A") (pintype "passive"))
      (node (ref "D26") (pin "A") (pinfunction "A_A") (pintype "passive"))
      (node (ref "D27") (pin "A") (pinfunction "A_A") (pintype "passive"))
      (node (ref "D28") (pin "A") (pinfunction "A_A") (pintype "passive"))
      (node (ref "D29") (pin "A") (pinfunction "A_A") (pintype "passive"))
      (node (ref "D3") (pin "A") (pinfunction "A_A") (pintype "passive"))
      (node (ref "D30") (pin "A") (pinfunction "A_A") (pintype "passive"))
      (node (ref "D31") (pin "A") (pinfunction "A_A") (pintype "passive"))
      (node (ref "D32") (pin "A") (pinfunction "A_A") (pintype "passive"))
      (node (ref "D33") (pin "A") (pinfunction "A_A") (pintype "passive"))
      (node (ref "D34") (pin "A") (pinfunction "A_A") (pintype "passive"))
      (node (ref "D35") (pin "A") (pinfunction "A_A") (pintype "passive"))
      (node (ref "D36") (pin "A") (pinfunction "A_A") (pintype "passive"))
      (node (ref "D37") (pin "A") (pinfunction "A_A") (pintype "passive"))
      (node (ref "D4") (pin "A") (pinfunction "A_A") (pintype "passive"))
      (node (ref "D5") (pin "A") (pinfunction "A_A") (pintype "passive"))
      (node (ref "D6") (pin "A") (pinfunction "A_A") (pintype "passive"))
      (node (ref "D7") (pin "A") (pinfunction "A_A") (pintype "passive"))
      (node (ref "D8") (pin "A") (pinfunction "A_A") (pintype "passive"))
      (node (ref "D9") (pin "A") (pinfunction "A_A") (pintype "passive"))
      (node (ref "IC1") (pin "6") (pinfunction "INH_6") (pintype "input"))
      (node (ref "IC2") (pin "6") (pinfunction "INH_6") (pintype "input"))
      (node (ref "IC3") (pin "6") (pinfunction "INH_6") (pintype "input"))
      (node (ref "IC4") (pin "6") (pinfunction "INH_6") (pintype "input"))
      (node (ref "J1") (pin "2EARTH") (pinfunction "EARTH_2EARTH") (pintype "bidirectional"))
      (node (ref "J1") (pin "EARTH") (pinfunction "EARTH_EARTH") (pintype "bidirectional"))
      (node (ref "J10") (pin "2EARTH") (pinfunction "EARTH_2EARTH") (pintype "bidirectional"))
      (node (ref "J10") (pin "EARTH") (pinfunction "EARTH_EARTH") (pintype "bidirectional"))
      (node (ref "J11") (pin "2EARTH") (pinfunction "EARTH_2EARTH") (pintype "bidirectional"))
      (node (ref "J11") (pin "EARTH") (pinfunction "EARTH_EARTH") (pintype "bidirectional"))
      (node (ref "J12") (pin "2EARTH") (pinfunction "EARTH_2EARTH") (pintype "bidirectional"))
      (node (ref "J12") (pin "EARTH") (pinfunction "EARTH_EARTH") (pintype "bidirectional"))
      (node (ref "J13") (pin "2EARTH") (pinfunction "EARTH_2EARTH") (pintype "bidirectional"))
      (node (ref "J13") (pin "EARTH") (pinfunction "EARTH_EARTH") (pintype "bidirectional"))
      (node (ref "J14") (pin "2EARTH") (pinfunction "EARTH_2EARTH") (pintype "bidirectional"))
      (node (ref "J14") (pin "EARTH") (pinfunction "EARTH_EARTH") (pintype "bidirectional"))
      (node (ref "J15") (pin "2EARTH") (pinfunction "EARTH_2EARTH") (pintype "bidirectional"))
      (node (ref "J15") (pin "EARTH") (pinfunction "EARTH_EARTH") (pintype "bidirectional"))
      (node (ref "J16") (pin "2EARTH") (pinfunction "EARTH_2EARTH") (pintype "bidirectional"))
      (node (ref "J16") (pin "EARTH") (pinfunction "EARTH_EARTH") (pintype "bidirectional"))
      (node (ref "J17") (pin "2EARTH") (pinfunction "EARTH_2EARTH") (pintype "bidirectional"))
      (node (ref "J17") (pin "EARTH") (pinfunction "EARTH_EARTH") (pintype "bidirectional"))
      (node (ref "J18") (pin "2EARTH") (pinfunction "EARTH_2EARTH") (pintype "bidirectional"))
      (node (ref "J18") (pin "EARTH") (pinfunction "EARTH_EARTH") (pintype "bidirectional"))
      (node (ref "J2") (pin "2EARTH") (pinfunction "EARTH_2EARTH") (pintype "bidirectional"))
      (node (ref "J2") (pin "EARTH") (pinfunction "EARTH_EARTH") (pintype "bidirectional"))
      (node (ref "J3") (pin "2EARTH") (pinfunction "EARTH_2EARTH") (pintype "bidirectional"))
      (node (ref "J3") (pin "EARTH") (pinfunction "EARTH_EARTH") (pintype "bidirectional"))
      (node (ref "J4") (pin "2EARTH") (pinfunction "EARTH_2EARTH") (pintype "bidirectional"))
      (node (ref "J4") (pin "EARTH") (pinfunction "EARTH_EARTH") (pintype "bidirectional"))
      (node (ref "J5") (pin "2EARTH") (pinfunction "EARTH_2EARTH") (pintype "bidirectional"))
      (node (ref "J5") (pin "EARTH") (pinfunction "EARTH_EARTH") (pintype "bidirectional"))
      (node (ref "J6") (pin "2EARTH") (pinfunction "EARTH_2EARTH") (pintype "bidirectional"))
      (node (ref "J6") (pin "EARTH") (pinfunction "EARTH_EARTH") (pintype "bidirectional"))
      (node (ref "J7") (pin "2EARTH") (pinfunction "EARTH_2EARTH") (pintype "bidirectional"))
      (node (ref "J7") (pin "EARTH") (pinfunction "EARTH_EARTH") (pintype "bidirectional"))
      (node (ref "J8") (pin "2EARTH") (pinfunction "EARTH_2EARTH") (pintype "bidirectional"))
      (node (ref "J8") (pin "EARTH") (pinfunction "EARTH_EARTH") (pintype "bidirectional"))
      (node (ref "J9") (pin "2EARTH") (pinfunction "EARTH_2EARTH") (pintype "bidirectional"))
      (node (ref "J9") (pin "EARTH") (pinfunction "EARTH_EARTH") (pintype "bidirectional"))
      (node (ref "R1") (pin "1") (pinfunction "1_1") (pintype "passive"))
      (node (ref "R10") (pin "1") (pinfunction "1_1") (pintype "passive"))
      (node (ref "R11") (pin "1") (pinfunction "1_1") (pintype "passive"))
      (node (ref "R12") (pin "1") (pinfunction "1_1") (pintype "passive"))
      (node (ref "R13") (pin "1") (pinfunction "1_1") (pintype "passive"))
      (node (ref "R14") (pin "1") (pinfunction "1_1") (pintype "passive"))
      (node (ref "R15") (pin "1") (pinfunction "1_1") (pintype "passive"))
      (node (ref "R16") (pin "1") (pinfunction "1_1") (pintype "passive"))
      (node (ref "R17") (pin "1") (pinfunction "1_1") (pintype "passive"))
      (node (ref "R18") (pin "1") (pinfunction "1_1") (pintype "passive"))
      (node (ref "R19") (pin "1") (pinfunction "1_1") (pintype "passive"))
      (node (ref "R2") (pin "1") (pinfunction "1_1") (pintype "passive"))
      (node (ref "R20") (pin "1") (pinfunction "1_1") (pintype "passive"))
      (node (ref "R21") (pin "1") (pinfunction "1_1") (pintype "passive"))
      (node (ref "R22") (pin "1") (pinfunction "1_1") (pintype "passive"))
      (node (ref "R23") (pin "1") (pinfunction "1_1") (pintype "passive"))
      (node (ref "R24") (pin "1") (pinfunction "1_1") (pintype "passive"))
      (node (ref "R25") (pin "1") (pinfunction "1_1") (pintype "passive"))
      (node (ref "R26") (pin "1") (pinfunction "1_1") (pintype "passive"))
      (node (ref "R27") (pin "1") (pinfunction "1_1") (pintype "passive"))
      (node (ref "R28") (pin "1") (pinfunction "1_1") (pintype "passive"))
      (node (ref "R29") (pin "1") (pinfunction "1_1") (pintype "passive"))
      (node (ref "R3") (pin "1") (pinfunction "1_1") (pintype "passive"))
      (node (ref "R30") (pin "1") (pinfunction "1_1") (pintype "passive"))
      (node (ref "R31") (pin "1") (pinfunction "1_1") (pintype "passive"))
      (node (ref "R32") (pin "1") (pinfunction "1_1") (pintype "passive"))
      (node (ref "R33") (pin "1") (pinfunction "1_1") (pintype "passive"))
      (node (ref "R34") (pin "1") (pinfunction "1_1") (pintype "passive"))
      (node (ref "R35") (pin "1") (pinfunction "1_1") (pintype "passive"))
      (node (ref "R36") (pin "1") (pinfunction "1_1") (pintype "passive"))
      (node (ref "R37") (pin "1") (pinfunction "1_1") (pintype "passive"))
      (node (ref "R4") (pin "1") (pinfunction "1_1") (pintype "passive"))
      (node (ref "R5") (pin "1") (pinfunction "1_1") (pintype "passive"))
      (node (ref "R6") (pin "1") (pinfunction "1_1") (pintype "passive"))
      (node (ref "R7") (pin "1") (pinfunction "1_1") (pintype "passive"))
      (node (ref "R8") (pin "1") (pinfunction "1_1") (pintype "passive"))
      (node (ref "R9") (pin "1") (pinfunction "1_1") (pintype "passive"))
      (node (ref "S1") (pin "2") (pinfunction "2_2") (pintype "passive"))
    )
    (net (code "50") (name "Net-(ARDUINO-RESET)") (class "Default")
      (node (ref "ARDUINO") (pin "22") (pinfunction "RESET_22") (pintype "bidirectional"))
      (node (ref "S1") (pin "1") (pinfunction "1_1") (pintype "passive"))
    )
    (net (code "51") (name "Net-(J1-PadRING1)") (class "Default")
      (node (ref "J1") (pin "RING1") (pinfunction "RING1_RING1") (pintype "bidirectional"))
      (node (ref "R38") (pin "1") (pinfunction "1_1") (pintype "passive"))
    )
    (net (code "52") (name "VCC") (class "Default")
      (node (ref "ARDUINO") (pin "21") (pinfunction "VCC_21") (pintype "bidirectional"))
      (node (ref "R38") (pin "2") (pinfunction "2_2") (pintype "passive"))
    )
    (net (code "53") (name "unconnected-(ARDUINO-RAW-Pad24)") (class "Default")
      (node (ref "ARDUINO") (pin "24") (pinfunction "RAW_24") (pintype "bidirectional"))
    )
    (net (code "54") (name "unconnected-(ARDUINO-RXI-Pad2)") (class "Default")
      (node (ref "ARDUINO") (pin "2") (pinfunction "RXI_2") (pintype "bidirectional"))
    )
    (net (code "55") (name "unconnected-(ARDUINO-TXO-Pad1)") (class "Default")
      (node (ref "ARDUINO") (pin "1") (pinfunction "TXO_1") (pintype "bidirectional"))
    )
    (net (code "56") (name "unconnected-(J1-PadRING2)") (class "Default")
      (node (ref "J1") (pin "RING2") (pinfunction "RING2_RING2") (pintype "bidirectional"))
    )
    (net (code "57") (name "unconnected-(J2-PadRING2)") (class "Default")
      (node (ref "J2") (pin "RING2") (pinfunction "RING2_RING2") (pintype "bidirectional"))
    )
    (net (code "58") (name "unconnected-(J3-PadRING1)") (class "Default")
      (node (ref "J3") (pin "RING1") (pinfunction "RING1_RING1") (pintype "bidirectional"))
    )
    (net (code "59") (name "unconnected-(J3-PadRING2)") (class "Default")
      (node (ref "J3") (pin "RING2") (pinfunction "RING2_RING2") (pintype "bidirectional"))
    )
    (net (code "60") (name "unconnected-(J4-PadRING2)") (class "Default")
      (node (ref "J4") (pin "RING2") (pinfunction "RING2_RING2") (pintype "bidirectional"))
    )
    (net (code "61") (name "unconnected-(J5-PadRING2)") (class "Default")
      (node (ref "J5") (pin "RING2") (pinfunction "RING2_RING2") (pintype "bidirectional"))
    )
    (net (code "62") (name "unconnected-(J6-PadRING2)") (class "Default")
      (node (ref "J6") (pin "RING2") (pinfunction "RING2_RING2") (pintype "bidirectional"))
    )
    (net (code "63") (name "unconnected-(J7-PadRING2)") (class "Default")
      (node (ref "J7") (pin "RING2") (pinfunction "RING2_RING2") (pintype "bidirectional"))
    )
    (net (code "64") (name "unconnected-(J8-PadRING2)") (class "Default")
      (node (ref "J8") (pin "RING2") (pinfunction "RING2_RING2") (pintype "bidirectional"))
    )
    (net (code "65") (name "unconnected-(J9-PadRING2)") (class "Default")
      (node (ref "J9") (pin "RING2") (pinfunction "RING2_RING2") (pintype "bidirectional"))
    )
    (net (code "66") (name "unconnected-(J10-PadRING2)") (class "Default")
      (node (ref "J10") (pin "RING2") (pinfunction "RING2_RING2") (pintype "bidirectional"))
    )
    (net (code "67") (name "unconnected-(J14-PadRING2)") (class "Default")
      (node (ref "J14") (pin "RING2") (pinfunction "RING2_RING2") (pintype "bidirectional"))
    )
    (net (code "68") (name "unconnected-(J15-PadRING2)") (class "Default")
      (node (ref "J15") (pin "RING2") (pinfunction "RING2_RING2") (pintype "bidirectional"))
    )
    (net (code "69") (name "unconnected-(J16-PadRING2)") (class "Default")
      (node (ref "J16") (pin "RING2") (pinfunction "RING2_RING2") (pintype "bidirectional"))
    )
    (net (code "70") (name "unconnected-(J17-PadRING2)") (class "Default")
      (node (ref "J17") (pin "RING2") (pinfunction "RING2_RING2") (pintype "bidirectional"))
    )
    (net (code "71") (name "unconnected-(J18-PadRING2)") (class "Default")
      (node (ref "J18") (pin "RING2") (pinfunction "RING2_RING2") (pintype "bidirectional"))
    )
  )
)
